# Fonte_Sim_Bat.net
KiCad netlist of a schematic drawn in Altium Designer
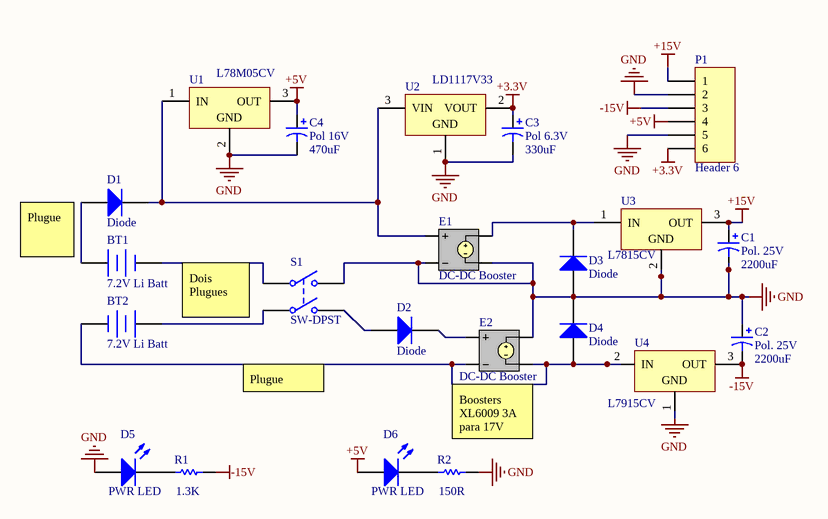
[diagram p0: Fonte_Sim_Bat.SchDoc]

(export (version "E")
  (design (tool "Eeschema 10.0.6"))
  (components
    (comp (ref "BT1")
      (value "7.2V Li Batt")
      (footprint "BAT-2")
      (description "Multicell Battery")
      (fields (field (name "PUBLISHER") "Altium Limited"))
      (libsource (lib "Miscellaneous Devices") (part "Battery"))
    )
    (comp (ref "BT2")
      (value "7.2V Li Batt")
      (footprint "BAT-2")
      (description "Multicell Battery")
      (fields (field (name "PUBLISHER") "Altium Limited"))
      (libsource (lib "Miscellaneous Devices") (part "Battery"))
    )
    (comp (ref "C1")
      (value "Pol. 25V")
      (footprint "RB7.6-15")
      (description "Polarized Capacitor (Radial)")
      (fields (field (name "ALTIUM_VALUE") "2200uF") (field (name "PUBLISHER") "Altium Limited"))
      (libsource (lib "Miscellaneous Devices") (part "Cap Pol1"))
    )
    (comp (ref "C2")
      (value "Pol. 25V")
      (footprint "RB7.6-15")
      (description "Polarized Capacitor (Radial)")
      (fields (field (name "ALTIUM_VALUE") "2200uF") (field (name "PUBLISHER") "Altium Limited"))
      (libsource (lib "Miscellaneous Devices") (part "Cap Pol1"))
    )
    (comp (ref "C3")
      (value "Pol 6.3V")
      (footprint "RB7.6-15")
      (description "Polarized Capacitor (Radial)")
      (fields (field (name "ALTIUM_VALUE") "330uF") (field (name "PUBLISHER") "Altium Limited"))
      (libsource (lib "Miscellaneous Devices") (part "Cap Pol1"))
    )
    (comp (ref "C4")
      (value "Pol 16V")
      (footprint "RB7.6-15")
      (description "Polarized Capacitor (Radial)")
      (fields (field (name "ALTIUM_VALUE") "470uF") (field (name "PUBLISHER") "Altium Limited"))
      (libsource (lib "Miscellaneous Devices") (part "Cap Pol1"))
    )
    (comp (ref "D1")
      (value "Diode")
      (footprint "SMC")
      (description "2A or greater, to prevent reverse polarity")
      (fields (field (name "PUBLISHER") "Altium Limited"))
      (libsource (lib "Miscellaneous Devices") (part "Diode"))
    )
    (comp (ref "D2")
      (value "Diode")
      (footprint "SMC")
      (description "2A or greater, to prevent reverse polarity")
      (fields (field (name "PUBLISHER") "Altium Limited"))
      (libsource (lib "Miscellaneous Devices") (part "Diode"))
    )
    (comp (ref "D3")
      (value "Diode")
      (footprint "SMC")
      (description "Flywheel")
      (fields (field (name "PUBLISHER") "Altium Limited"))
      (libsource (lib "Miscellaneous Devices") (part "Diode"))
    )
    (comp (ref "D4")
      (value "Diode")
      (footprint "SMC")
      (description "Flywheel")
      (fields (field (name "PUBLISHER") "Altium Limited"))
      (libsource (lib "Miscellaneous Devices") (part "Diode"))
    )
    (comp (ref "D5")
      (value "PWR LED")
      (footprint "3.5X2.8X1.9")
      (description "Typical BLUE SiC LED")
      (fields (field (name "PUBLISHER") "Altium Limited"))
      (libsource (lib "Miscellaneous Devices") (part "LED3"))
    )
    (comp (ref "D6")
      (value "PWR LED")
      (footprint "3.5X2.8X1.9")
      (description "Typical BLUE SiC LED")
      (fields (field (name "PUBLISHER") "Altium Limited"))
      (libsource (lib "Miscellaneous Devices") (part "LED3"))
    )
    (comp (ref "E1")
      (value "DC-DC Booster")
      (description "Voltage Controlled Voltage Source")
      (fields (field (name "PUBLISHER") "Altium Limited"))
      (libsource (lib "Simulation Sources") (part "ESRC"))
    )
    (comp (ref "E2")
      (value "DC-DC Booster")
      (description "Voltage Controlled Voltage Source")
      (fields (field (name "PUBLISHER") "Altium Limited"))
      (libsource (lib "Simulation Sources") (part "ESRC"))
    )
    (comp (ref "P1")
      (value "Header 6")
      (footprint "HDR1X6")
      (description "Header, 6-Pin")
      (fields (field (name "PUBLISHER") "Altium Limited"))
      (libsource (lib "Miscellaneous Connectors") (part "Header 6"))
    )
    (comp (ref "R1")
      (value "1.3K")
      (footprint "AXIAL-0.3")
      (description "Resistor")
      (fields (field (name "PUBLISHER") "Altium Limited"))
      (libsource (lib "Miscellaneous Devices") (part "Res1"))
    )
    (comp (ref "R2")
      (value "150R")
      (footprint "AXIAL-0.3")
      (description "Resistor")
      (fields (field (name "PUBLISHER") "Altium Limited"))
      (libsource (lib "Miscellaneous Devices") (part "Res1"))
    )
    (comp (ref "S1")
      (value "SW-DPST")
      (footprint "DPST-4")
      (description "Double-Pole, Single-Throw Switch")
      (fields (field (name "PUBLISHER") "Altium Limited"))
      (libsource (lib "Miscellaneous Devices") (part "SW-DPST"))
    )
    (comp (ref "U1")
      (value "L78M05CV")
      (footprint "TO220")
      (description "Positive Voltage Regulator, 5V, 3-Pin TO-220")
      (libsource (lib "Power Management Linear Regulator-STMicroelectronics") (part "L78M05CV"))
    )
    (comp (ref "U2")
      (value "LD1117V33")
      (footprint "TO220")
      (description "Fixed Low Drop Positive Voltage Regulator, 3.3V, 3-Pin TO-220")
      (libsource (lib "Power Management Linear Regulator-STMicroelectronics") (part "LD1117V33"))
    )
    (comp (ref "U3")
      (value "L7815CV")
      (footprint "TO220")
      (description "Positive Voltage Regulator, 15V, 3-Pin TO-220")
      (libsource (lib "Power Management Linear Regulator-STMicroelectronics") (part "L7815CV"))
    )
    (comp (ref "U4")
      (value "L7915CV")
      (footprint "TO-220")
      (description "Negative Voltage Regulator, -15V, 3-Pin D2PAK")
      (libsource (lib "Power Management Linear Regulator-STMicroelectronics") (part "L7915CV"))
    )
  )
  (nets
    (net (code "1") (name "+3.3V") (class "Default")
      (node (ref "C3") (pin "1") (pinfunction "1_1") (pintype "passive"))
      (node (ref "P1") (pin "6") (pinfunction "6_6") (pintype "passive"))
      (node (ref "U2") (pin "2") (pinfunction "VOUT_2") (pintype "power_in"))
    )
    (net (code "2") (name "+5V") (class "Default")
      (node (ref "C4") (pin "1") (pinfunction "1_1") (pintype "passive"))
      (node (ref "D6") (pin "1") (pinfunction "A_1") (pintype "passive"))
      (node (ref "P1") (pin "4") (pinfunction "4_4") (pintype "passive"))
      (node (ref "U1") (pin "3") (pinfunction "OUT_3") (pintype "power_in"))
    )
    (net (code "3") (name "+15V") (class "Default")
      (node (ref "C1") (pin "1") (pinfunction "1_1") (pintype "passive"))
      (node (ref "P1") (pin "1") (pinfunction "1_1") (pintype "passive"))
      (node (ref "U3") (pin "3") (pinfunction "OUT_3") (pintype "power_in"))
    )
    (net (code "4") (name "-15V") (class "Default")
      (node (ref "C2") (pin "2") (pinfunction "2_2") (pintype "passive"))
      (node (ref "P1") (pin "3") (pinfunction "3_3") (pintype "passive"))
      (node (ref "R1") (pin "2") (pinfunction "2_2") (pintype "passive"))
      (node (ref "U4") (pin "3") (pinfunction "OUT_3") (pintype "power_in"))
    )
    (net (code "5") (name "GND") (class "Default")
      (node (ref "C1") (pin "2") (pinfunction "2_2") (pintype "passive"))
      (node (ref "C2") (pin "1") (pinfunction "1_1") (pintype "passive"))
      (node (ref "C3") (pin "2") (pinfunction "2_2") (pintype "passive"))
      (node (ref "C4") (pin "2") (pinfunction "2_2") (pintype "passive"))
      (node (ref "D3") (pin "1") (pinfunction "A_1") (pintype "passive"))
      (node (ref "D4") (pin "2") (pinfunction "K_2") (pintype "passive"))
      (node (ref "D5") (pin "1") (pinfunction "A_1") (pintype "passive"))
      (node (ref "E1") (pin "2") (pinfunction "NC-_2") (pintype "passive"))
      (node (ref "E1") (pin "4") (pinfunction "N-_4") (pintype "passive"))
      (node (ref "E2") (pin "3") (pinfunction "N+_3") (pintype "passive"))
      (node (ref "P1") (pin "2") (pinfunction "2_2") (pintype "passive"))
      (node (ref "P1") (pin "5") (pinfunction "5_5") (pintype "passive"))
      (node (ref "R2") (pin "2") (pinfunction "2_2") (pintype "passive"))
      (node (ref "S1") (pin "2") (pinfunction "NO1_2") (pintype "passive"))
      (node (ref "U1") (pin "2") (pinfunction "GND_2") (pintype "power_in"))
      (node (ref "U2") (pin "1") (pinfunction "GND_1") (pintype "power_in"))
      (node (ref "U3") (pin "2") (pinfunction "GND_2") (pintype "power_in"))
      (node (ref "U4") (pin "1") (pinfunction "GND_1") (pintype "power_in"))
    )
    (net (code "6") (name "Net-(BT1-+)") (class "Default")
      (node (ref "BT1") (pin "1") (pinfunction "+_1") (pintype "passive"))
      (node (ref "D1") (pin "1") (pinfunction "A_1") (pintype "passive"))
    )
    (net (code "7") (name "Net-(BT1--)") (class "Default")
      (node (ref "BT1") (pin "2") (pinfunction "-_2") (pintype "passive"))
      (node (ref "S1") (pin "1") (pinfunction "COMMON1_1") (pintype "passive"))
    )
    (net (code "8") (name "Net-(BT2-+)") (class "Default")
      (node (ref "BT2") (pin "1") (pinfunction "+_1") (pintype "passive"))
      (node (ref "S1") (pin "3") (pinfunction "COMMON2_3") (pintype "passive"))
    )
    (net (code "9") (name "Net-(BT2--)") (class "Default")
      (node (ref "BT2") (pin "2") (pinfunction "-_2") (pintype "passive"))
      (node (ref "D4") (pin "1") (pinfunction "A_1") (pintype "passive"))
      (node (ref "E2") (pin "2") (pinfunction "NC-_2") (pintype "passive"))
      (node (ref "E2") (pin "4") (pinfunction "N-_4") (pintype "passive"))
      (node (ref "U4") (pin "2") (pinfunction "IN_2") (pintype "power_in"))
    )
    (net (code "10") (name "Net-(D1-K)") (class "Default")
      (node (ref "D1") (pin "2") (pinfunction "K_2") (pintype "passive"))
      (node (ref "E1") (pin "1") (pinfunction "NC+_1") (pintype "passive"))
      (node (ref "U1") (pin "1") (pinfunction "IN_1") (pintype "power_in"))
      (node (ref "U2") (pin "3") (pinfunction "VIN_3") (pintype "power_in"))
    )
    (net (code "11") (name "Net-(D2-A)") (class "Default")
      (node (ref "D2") (pin "1") (pinfunction "A_1") (pintype "passive"))
      (node (ref "S1") (pin "4") (pinfunction "NO2_4") (pintype "passive"))
    )
    (net (code "12") (name "Net-(D2-K)") (class "Default")
      (node (ref "D2") (pin "2") (pinfunction "K_2") (pintype "passive"))
      (node (ref "E2") (pin "1") (pinfunction "NC+_1") (pintype "passive"))
    )
    (net (code "13") (name "Net-(D3-K)") (class "Default")
      (node (ref "D3") (pin "2") (pinfunction "K_2") (pintype "passive"))
      (node (ref "E1") (pin "3") (pinfunction "N+_3") (pintype "passive"))
      (node (ref "U3") (pin "1") (pinfunction "IN_1") (pintype "power_in"))
    )
    (net (code "14") (name "Net-(D5-K)") (class "Default")
      (node (ref "D5") (pin "2") (pinfunction "K_2") (pintype "passive"))
      (node (ref "R1") (pin "1") (pinfunction "1_1") (pintype "passive"))
    )
    (net (code "15") (name "Net-(D6-K)") (class "Default")
      (node (ref "D6") (pin "2") (pinfunction "K_2") (pintype "passive"))
      (node (ref "R2") (pin "1") (pinfunction "1_1") (pintype "passive"))
    )
  )
)
